# aux_board.net
KiCad netlist of a schematic drawn in EAGLE
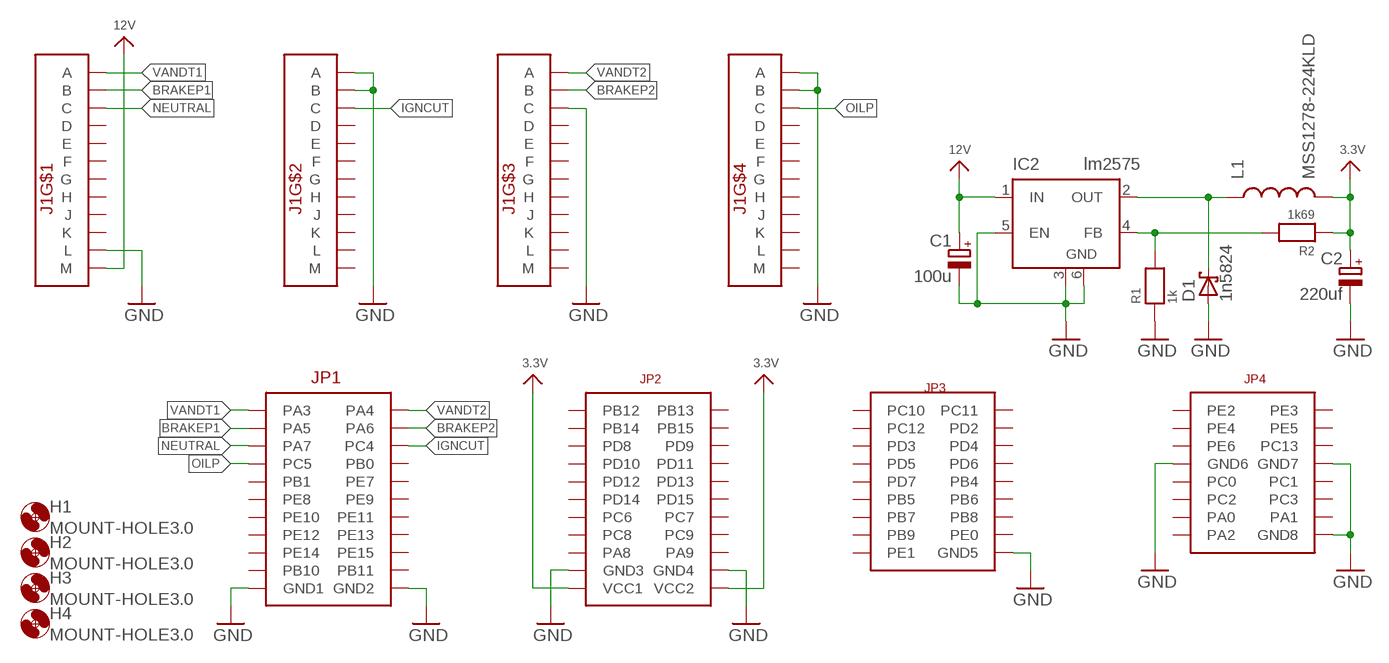
[diagram p0: schematic, sheet 1]

(export (version "E")
  (design (tool "Eeschema 10.0.6"))
  (components
    (comp (ref "C1")
      (value "100u")
      (footprint "eagle-import:E2,5-7")
      (libsource (lib "eagle-import") (part "CPOL-EUE2.5-7"))
    )
    (comp (ref "C2")
      (value "220uf")
      (footprint "eagle-import:E3,5-8")
      (libsource (lib "eagle-import") (part "CPOL-EUE3.5-8"))
    )
    (comp (ref "D1")
      (value "1n5824")
      (footprint "eagle-import:F126Z12")
      (libsource (lib "eagle-import") (part "SCHOTTKY-DIODEF126Z12"))
    )
    (comp (ref "H1")
      (value "MOUNT-HOLE3.0")
      (footprint "eagle-import:3,0")
      (libsource (lib "eagle-import") (part "MOUNT-HOLE3.0"))
    )
    (comp (ref "H2")
      (value "MOUNT-HOLE3.0")
      (footprint "eagle-import:3,0")
      (libsource (lib "eagle-import") (part "MOUNT-HOLE3.0"))
    )
    (comp (ref "H3")
      (value "MOUNT-HOLE3.0")
      (footprint "eagle-import:3,0")
      (libsource (lib "eagle-import") (part "MOUNT-HOLE3.0"))
    )
    (comp (ref "H4")
      (value "MOUNT-HOLE3.0")
      (footprint "eagle-import:3,0")
      (libsource (lib "eagle-import") (part "MOUNT-HOLE3.0"))
    )
    (comp (ref "IC2")
      (value "lm2575")
      (footprint "eagle-import:TO263-5")
      (libsource (lib "eagle-import") (part "LM2596S"))
    )
    (comp (ref "J1")
      (value "AUTOCONNECTOR")
      (footprint "eagle-import:AUTOCONNECTOR")
      (libsource (lib "eagle-import") (part "AUTOCONNECTOR"))
    )
    (comp (ref "L1")
      (value "MSS1278-224KLD")
      (footprint "eagle-import:CDRH125")
      (libsource (lib "eagle-import") (part "INDUCTORPWR"))
    )
    (comp (ref "R1")
      (value "1k")
      (footprint "eagle-import:_0603")
      (libsource (lib "eagle-import") (part "RESISTOR_0603"))
    )
    (comp (ref "R2")
      (value "1k69")
      (footprint "eagle-import:_0603")
      (libsource (lib "eagle-import") (part "RESISTOR_0603"))
    )
    (comp (ref "U$1")
      (value "CPU-BOARD")
      (footprint "eagle-import:CPU-BOARD-JP1")
      (libsource (lib "eagle-import") (part "CPU-BOARD"))
    )
  )
  (nets
    (net (code "1") (name "3.3V") (class "Default")
      (node (ref "C2") (pin "+") (pinfunction "+_+") (pintype "passive"))
      (node (ref "L1") (pin "2") (pinfunction "2_2") (pintype "passive"))
      (node (ref "R2") (pin "1") (pinfunction "1_1") (pintype "passive"))
      (node (ref "U$1") (pin "P$43") (pinfunction "VCC1_P$43") (pintype "bidirectional"))
      (node (ref "U$1") (pin "P$44") (pinfunction "VCC2_P$44") (pintype "bidirectional"))
    )
    (net (code "2") (name "12V") (class "Default")
      (node (ref "C1") (pin "+") (pinfunction "+_+") (pintype "passive"))
      (node (ref "IC2") (pin "1") (pinfunction "IN_1") (pintype "input"))
      (node (ref "J1") (pin "M1") (pinfunction "M_M1") (pintype "bidirectional"))
    )
    (net (code "3") (name "BRAKEP1") (class "Default")
      (node (ref "J1") (pin "B1") (pinfunction "B_B1") (pintype "bidirectional"))
      (node (ref "U$1") (pin "P$3") (pinfunction "PA5_P$3") (pintype "bidirectional"))
    )
    (net (code "4") (name "BRAKEP2") (class "Default")
      (node (ref "J1") (pin "B3") (pinfunction "B_B3") (pintype "bidirectional"))
      (node (ref "U$1") (pin "P$4") (pinfunction "PA6_P$4") (pintype "bidirectional"))
    )
    (net (code "5") (name "GND") (class "Default")
      (node (ref "C1") (pin "-") (pinfunction "-_-") (pintype "passive"))
      (node (ref "C2") (pin "-") (pinfunction "-_-") (pintype "passive"))
      (node (ref "D1") (pin "A") (pinfunction "A_A") (pintype "passive"))
      (node (ref "IC2") (pin "3") (pinfunction "GND_3") (pintype "power_in"))
      (node (ref "IC2") (pin "5") (pinfunction "EN_5") (pintype "input"))
      (node (ref "IC2") (pin "6") (pinfunction "GND_6") (pintype "power_in"))
      (node (ref "J1") (pin "A2") (pinfunction "A_A2") (pintype "bidirectional"))
      (node (ref "J1") (pin "A4") (pinfunction "A_A4") (pintype "bidirectional"))
      (node (ref "J1") (pin "B2") (pinfunction "B_B2") (pintype "bidirectional"))
      (node (ref "J1") (pin "B4") (pinfunction "B_B4") (pintype "bidirectional"))
      (node (ref "J1") (pin "C3") (pinfunction "C_C3") (pintype "bidirectional"))
      (node (ref "J1") (pin "L1") (pinfunction "L_L1") (pintype "bidirectional"))
      (node (ref "R1") (pin "1") (pinfunction "1_1") (pintype "passive"))
      (node (ref "U$1") (pin "P$21") (pinfunction "GND1_P$21") (pintype "bidirectional"))
      (node (ref "U$1") (pin "P$22") (pinfunction "GND2_P$22") (pintype "bidirectional"))
      (node (ref "U$1") (pin "P$41") (pinfunction "GND3_P$41") (pintype "bidirectional"))
      (node (ref "U$1") (pin "P$42") (pinfunction "GND4_P$42") (pintype "bidirectional"))
      (node (ref "U$1") (pin "P$62") (pinfunction "GND5_P$62") (pintype "bidirectional"))
      (node (ref "U$1") (pin "P$69") (pinfunction "GND6_P$69") (pintype "bidirectional"))
      (node (ref "U$1") (pin "P$70") (pinfunction "GND7_P$70") (pintype "bidirectional"))
      (node (ref "U$1") (pin "P$78") (pinfunction "GND8_P$78") (pintype "bidirectional"))
    )
    (net (code "6") (name "IGNCUT") (class "Default")
      (node (ref "J1") (pin "C2") (pinfunction "C_C2") (pintype "bidirectional"))
      (node (ref "U$1") (pin "P$6") (pinfunction "PC4_P$6") (pintype "bidirectional"))
    )
    (net (code "7") (name "NEUTRAL") (class "Default")
      (node (ref "J1") (pin "C1") (pinfunction "C_C1") (pintype "bidirectional"))
      (node (ref "U$1") (pin "P$5") (pinfunction "PA7_P$5") (pintype "bidirectional"))
    )
    (net (code "8") (name "Net-(IC2-FB)") (class "Default")
      (node (ref "IC2") (pin "4") (pinfunction "FB_4") (pintype "input"))
      (node (ref "R1") (pin "2") (pinfunction "2_2") (pintype "passive"))
      (node (ref "R2") (pin "2") (pinfunction "2_2") (pintype "passive"))
    )
    (net (code "9") (name "Net-(IC2-OUT)") (class "Default")
      (node (ref "D1") (pin "C") (pinfunction "C_C") (pintype "passive"))
      (node (ref "IC2") (pin "2") (pinfunction "OUT_2") (pintype "output"))
      (node (ref "L1") (pin "1") (pinfunction "1_1") (pintype "passive"))
    )
    (net (code "10") (name "OILP") (class "Default")
      (node (ref "J1") (pin "C4") (pinfunction "C_C4") (pintype "bidirectional"))
      (node (ref "U$1") (pin "P$7") (pinfunction "PC5_P$7") (pintype "bidirectional"))
    )
    (net (code "11") (name "VANDT1") (class "Default")
      (node (ref "J1") (pin "A1") (pinfunction "A_A1") (pintype "bidirectional"))
      (node (ref "U$1") (pin "P$1") (pinfunction "PA3_P$1") (pintype "bidirectional"))
    )
    (net (code "12") (name "VANDT2") (class "Default")
      (node (ref "J1") (pin "A3") (pinfunction "A_A3") (pintype "bidirectional"))
      (node (ref "U$1") (pin "P$2") (pinfunction "PA4_P$2") (pintype "bidirectional"))
    )
    (net (code "13") (name "unconnected-(J1A-D-PadD1)") (class "Default")
      (node (ref "J1") (pin "D1") (pinfunction "D_D1") (pintype "bidirectional"))
    )
    (net (code "14") (name "unconnected-(J1A-E-PadE1)") (class "Default")
      (node (ref "J1") (pin "E1") (pinfunction "E_E1") (pintype "bidirectional"))
    )
    (net (code "15") (name "unconnected-(J1A-F-PadF1)") (class "Default")
      (node (ref "J1") (pin "F1") (pinfunction "F_F1") (pintype "bidirectional"))
    )
    (net (code "16") (name "unconnected-(J1A-G-PadG1)") (class "Default")
      (node (ref "J1") (pin "G1") (pinfunction "G_G1") (pintype "bidirectional"))
    )
    (net (code "17") (name "unconnected-(J1A-H-PadH1)") (class "Default")
      (node (ref "J1") (pin "H1") (pinfunction "H_H1") (pintype "bidirectional"))
    )
    (net (code "18") (name "unconnected-(J1A-J-PadJ1)") (class "Default")
      (node (ref "J1") (pin "J1") (pinfunction "J_J1") (pintype "bidirectional"))
    )
    (net (code "19") (name "unconnected-(J1A-K-PadK1)") (class "Default")
      (node (ref "J1") (pin "K1") (pinfunction "K_K1") (pintype "bidirectional"))
    )
    (net (code "20") (name "unconnected-(J1B-D-PadD2)") (class "Default")
      (node (ref "J1") (pin "D2") (pinfunction "D_D2") (pintype "bidirectional"))
    )
    (net (code "21") (name "unconnected-(J1B-E-PadE2)") (class "Default")
      (node (ref "J1") (pin "E2") (pinfunction "E_E2") (pintype "bidirectional"))
    )
    (net (code "22") (name "unconnected-(J1B-F-PadF2)") (class "Default")
      (node (ref "J1") (pin "F2") (pinfunction "F_F2") (pintype "bidirectional"))
    )
    (net (code "23") (name "unconnected-(J1B-G-PadG2)") (class "Default")
      (node (ref "J1") (pin "G2") (pinfunction "G_G2") (pintype "bidirectional"))
    )
    (net (code "24") (name "unconnected-(J1B-H-PadH2)") (class "Default")
      (node (ref "J1") (pin "H2") (pinfunction "H_H2") (pintype "bidirectional"))
    )
    (net (code "25") (name "unconnected-(J1B-J-PadJ2)") (class "Default")
      (node (ref "J1") (pin "J2") (pinfunction "J_J2") (pintype "bidirectional"))
    )
    (net (code "26") (name "unconnected-(J1B-K-PadK2)") (class "Default")
      (node (ref "J1") (pin "K2") (pinfunction "K_K2") (pintype "bidirectional"))
    )
    (net (code "27") (name "unconnected-(J1B-L-PadL2)") (class "Default")
      (node (ref "J1") (pin "L2") (pinfunction "L_L2") (pintype "bidirectional"))
    )
    (net (code "28") (name "unconnected-(J1B-M-PadM2)") (class "Default")
      (node (ref "J1") (pin "M2") (pinfunction "M_M2") (pintype "bidirectional"))
    )
    (net (code "29") (name "unconnected-(J1C-D-PadD3)") (class "Default")
      (node (ref "J1") (pin "D3") (pinfunction "D_D3") (pintype "bidirectional"))
    )
    (net (code "30") (name "unconnected-(J1C-E-PadE3)") (class "Default")
      (node (ref "J1") (pin "E3") (pinfunction "E_E3") (pintype "bidirectional"))
    )
    (net (code "31") (name "unconnected-(J1C-F-PadF3)") (class "Default")
      (node (ref "J1") (pin "F3") (pinfunction "F_F3") (pintype "bidirectional"))
    )
    (net (code "32") (name "unconnected-(J1C-G-PadG3)") (class "Default")
      (node (ref "J1") (pin "G3") (pinfunction "G_G3") (pintype "bidirectional"))
    )
    (net (code "33") (name "unconnected-(J1C-H-PadH3)") (class "Default")
      (node (ref "J1") (pin "H3") (pinfunction "H_H3") (pintype "bidirectional"))
    )
    (net (code "34") (name "unconnected-(J1C-J-PadJ3)") (class "Default")
      (node (ref "J1") (pin "J3") (pinfunction "J_J3") (pintype "bidirectional"))
    )
    (net (code "35") (name "unconnected-(J1C-K-PadK3)") (class "Default")
      (node (ref "J1") (pin "K3") (pinfunction "K_K3") (pintype "bidirectional"))
    )
    (net (code "36") (name "unconnected-(J1C-L-PadL3)") (class "Default")
      (node (ref "J1") (pin "L3") (pinfunction "L_L3") (pintype "bidirectional"))
    )
    (net (code "37") (name "unconnected-(J1C-M-PadM3)") (class "Default")
      (node (ref "J1") (pin "M3") (pinfunction "M_M3") (pintype "bidirectional"))
    )
    (net (code "38") (name "unconnected-(J1D-D-PadD4)") (class "Default")
      (node (ref "J1") (pin "D4") (pinfunction "D_D4") (pintype "bidirectional"))
    )
    (net (code "39") (name "unconnected-(J1D-E-PadE4)") (class "Default")
      (node (ref "J1") (pin "E4") (pinfunction "E_E4") (pintype "bidirectional"))
    )
    (net (code "40") (name "unconnected-(J1D-F-PadF4)") (class "Default")
      (node (ref "J1") (pin "F4") (pinfunction "F_F4") (pintype "bidirectional"))
    )
    (net (code "41") (name "unconnected-(J1D-G-PadG4)") (class "Default")
      (node (ref "J1") (pin "G4") (pinfunction "G_G4") (pintype "bidirectional"))
    )
    (net (code "42") (name "unconnected-(J1D-H-PadH4)") (class "Default")
      (node (ref "J1") (pin "H4") (pinfunction "H_H4") (pintype "bidirectional"))
    )
    (net (code "43") (name "unconnected-(J1D-J-PadJ4)") (class "Default")
      (node (ref "J1") (pin "J4") (pinfunction "J_J4") (pintype "bidirectional"))
    )
    (net (code "44") (name "unconnected-(J1D-K-PadK4)") (class "Default")
      (node (ref "J1") (pin "K4") (pinfunction "K_K4") (pintype "bidirectional"))
    )
    (net (code "45") (name "unconnected-(J1D-L-PadL4)") (class "Default")
      (node (ref "J1") (pin "L4") (pinfunction "L_L4") (pintype "bidirectional"))
    )
    (net (code "46") (name "unconnected-(J1D-M-PadM4)") (class "Default")
      (node (ref "J1") (pin "M4") (pinfunction "M_M4") (pintype "bidirectional"))
    )
    (net (code "47") (name "unconnected-(U$1A-PB0-PadP$8)") (class "Default")
      (node (ref "U$1") (pin "P$8") (pinfunction "PB0_P$8") (pintype "bidirectional"))
    )
    (net (code "48") (name "unconnected-(U$1A-PB1-PadP$9)") (class "Default")
      (node (ref "U$1") (pin "P$9") (pinfunction "PB1_P$9") (pintype "bidirectional"))
    )
    (net (code "49") (name "unconnected-(U$1A-PB10-PadP$19)") (class "Default")
      (node (ref "U$1") (pin "P$19") (pinfunction "PB10_P$19") (pintype "bidirectional"))
    )
    (net (code "50") (name "unconnected-(U$1A-PB11-PadP$20)") (class "Default")
      (node (ref "U$1") (pin "P$20") (pinfunction "PB11_P$20") (pintype "bidirectional"))
    )
    (net (code "51") (name "unconnected-(U$1A-PE7-PadP$10)") (class "Default")
      (node (ref "U$1") (pin "P$10") (pinfunction "PE7_P$10") (pintype "bidirectional"))
    )
    (net (code "52") (name "unconnected-(U$1A-PE8-PadP$11)") (class "Default")
      (node (ref "U$1") (pin "P$11") (pinfunction "PE8_P$11") (pintype "bidirectional"))
    )
    (net (code "53") (name "unconnected-(U$1A-PE9-PadP$12)") (class "Default")
      (node (ref "U$1") (pin "P$12") (pinfunction "PE9_P$12") (pintype "bidirectional"))
    )
    (net (code "54") (name "unconnected-(U$1A-PE10-PadP$13)") (class "Default")
      (node (ref "U$1") (pin "P$13") (pinfunction "PE10_P$13") (pintype "bidirectional"))
    )
    (net (code "55") (name "unconnected-(U$1A-PE11-PadP$14)") (class "Default")
      (node (ref "U$1") (pin "P$14") (pinfunction "PE11_P$14") (pintype "bidirectional"))
    )
    (net (code "56") (name "unconnected-(U$1A-PE12-PadP$15)") (class "Default")
      (node (ref "U$1") (pin "P$15") (pinfunction "PE12_P$15") (pintype "bidirectional"))
    )
    (net (code "57") (name "unconnected-(U$1A-PE13-PadP$16)") (class "Default")
      (node (ref "U$1") (pin "P$16") (pinfunction "PE13_P$16") (pintype "bidirectional"))
    )
    (net (code "58") (name "unconnected-(U$1A-PE14-PadP$17)") (class "Default")
      (node (ref "U$1") (pin "P$17") (pinfunction "PE14_P$17") (pintype "bidirectional"))
    )
    (net (code "59") (name "unconnected-(U$1A-PE15-PadP$18)") (class "Default")
      (node (ref "U$1") (pin "P$18") (pinfunction "PE15_P$18") (pintype "bidirectional"))
    )
    (net (code "60") (name "unconnected-(U$1B-PA8-PadP$39)") (class "Default")
      (node (ref "U$1") (pin "P$39") (pinfunction "PA8_P$39") (pintype "bidirectional"))
    )
    (net (code "61") (name "unconnected-(U$1B-PA9-PadP$40)") (class "Default")
      (node (ref "U$1") (pin "P$40") (pinfunction "PA9_P$40") (pintype "bidirectional"))
    )
    (net (code "62") (name "unconnected-(U$1B-PB12-PadP$23)") (class "Default")
      (node (ref "U$1") (pin "P$23") (pinfunction "PB12_P$23") (pintype "bidirectional"))
    )
    (net (code "63") (name "unconnected-(U$1B-PB13-PadP$24)") (class "Default")
      (node (ref "U$1") (pin "P$24") (pinfunction "PB13_P$24") (pintype "bidirectional"))
    )
    (net (code "64") (name "unconnected-(U$1B-PB14-PadP$25)") (class "Default")
      (node (ref "U$1") (pin "P$25") (pinfunction "PB14_P$25") (pintype "bidirectional"))
    )
    (net (code "65") (name "unconnected-(U$1B-PB15-PadP$26)") (class "Default")
      (node (ref "U$1") (pin "P$26") (pinfunction "PB15_P$26") (pintype "bidirectional"))
    )
    (net (code "66") (name "unconnected-(U$1B-PC6-PadP$35)") (class "Default")
      (node (ref "U$1") (pin "P$35") (pinfunction "PC6_P$35") (pintype "bidirectional"))
    )
    (net (code "67") (name "unconnected-(U$1B-PC7-PadP$36)") (class "Default")
      (node (ref "U$1") (pin "P$36") (pinfunction "PC7_P$36") (pintype "bidirectional"))
    )
    (net (code "68") (name "unconnected-(U$1B-PC8-PadP$37)") (class "Default")
      (node (ref "U$1") (pin "P$37") (pinfunction "PC8_P$37") (pintype "bidirectional"))
    )
    (net (code "69") (name "unconnected-(U$1B-PC9-PadP$38)") (class "Default")
      (node (ref "U$1") (pin "P$38") (pinfunction "PC9_P$38") (pintype "bidirectional"))
    )
    (net (code "70") (name "unconnected-(U$1B-PD8-PadP$27)") (class "Default")
      (node (ref "U$1") (pin "P$27") (pinfunction "PD8_P$27") (pintype "bidirectional"))
    )
    (net (code "71") (name "unconnected-(U$1B-PD9-PadP$28)") (class "Default")
      (node (ref "U$1") (pin "P$28") (pinfunction "PD9_P$28") (pintype "bidirectional"))
    )
    (net (code "72") (name "unconnected-(U$1B-PD10-PadP$29)") (class "Default")
      (node (ref "U$1") (pin "P$29") (pinfunction "PD10_P$29") (pintype "bidirectional"))
    )
    (net (code "73") (name "unconnected-(U$1B-PD11-PadP$30)") (class "Default")
      (node (ref "U$1") (pin "P$30") (pinfunction "PD11_P$30") (pintype "bidirectional"))
    )
    (net (code "74") (name "unconnected-(U$1B-PD12-PadP$31)") (class "Default")
      (node (ref "U$1") (pin "P$31") (pinfunction "PD12_P$31") (pintype "bidirectional"))
    )
    (net (code "75") (name "unconnected-(U$1B-PD13-PadP$32)") (class "Default")
      (node (ref "U$1") (pin "P$32") (pinfunction "PD13_P$32") (pintype "bidirectional"))
    )
    (net (code "76") (name "unconnected-(U$1B-PD14-PadP$33)") (class "Default")
      (node (ref "U$1") (pin "P$33") (pinfunction "PD14_P$33") (pintype "bidirectional"))
    )
    (net (code "77") (name "unconnected-(U$1B-PD15-PadP$34)") (class "Default")
      (node (ref "U$1") (pin "P$34") (pinfunction "PD15_P$34") (pintype "bidirectional"))
    )
    (net (code "78") (name "unconnected-(U$1C-PB4-PadP$54)") (class "Default")
      (node (ref "U$1") (pin "P$54") (pinfunction "PB4_P$54") (pintype "bidirectional"))
    )
    (net (code "79") (name "unconnected-(U$1C-PB5-PadP$55)") (class "Default")
      (node (ref "U$1") (pin "P$55") (pinfunction "PB5_P$55") (pintype "bidirectional"))
    )
    (net (code "80") (name "unconnected-(U$1C-PB6-PadP$56)") (class "Default")
      (node (ref "U$1") (pin "P$56") (pinfunction "PB6_P$56") (pintype "bidirectional"))
    )
    (net (code "81") (name "unconnected-(U$1C-PB7-PadP$57)") (class "Default")
      (node (ref "U$1") (pin "P$57") (pinfunction "PB7_P$57") (pintype "bidirectional"))
    )
    (net (code "82") (name "unconnected-(U$1C-PB8-PadP$58)") (class "Default")
      (node (ref "U$1") (pin "P$58") (pinfunction "PB8_P$58") (pintype "bidirectional"))
    )
    (net (code "83") (name "unconnected-(U$1C-PB9-PadP$59)") (class "Default")
      (node (ref "U$1") (pin "P$59") (pinfunction "PB9_P$59") (pintype "bidirectional"))
    )
    (net (code "84") (name "unconnected-(U$1C-PC10-PadP$45)") (class "Default")
      (node (ref "U$1") (pin "P$45") (pinfunction "PC10_P$45") (pintype "bidirectional"))
    )
    (net (code "85") (name "unconnected-(U$1C-PC11-PadP$46)") (class "Default")
      (node (ref "U$1") (pin "P$46") (pinfunction "PC11_P$46") (pintype "bidirectional"))
    )
    (net (code "86") (name "unconnected-(U$1C-PC12-PadP$47)") (class "Default")
      (node (ref "U$1") (pin "P$47") (pinfunction "PC12_P$47") (pintype "bidirectional"))
    )
    (net (code "87") (name "unconnected-(U$1C-PD2-PadP$48)") (class "Default")
      (node (ref "U$1") (pin "P$48") (pinfunction "PD2_P$48") (pintype "bidirectional"))
    )
    (net (code "88") (name "unconnected-(U$1C-PD3-PadP$49)") (class "Default")
      (node (ref "U$1") (pin "P$49") (pinfunction "PD3_P$49") (pintype "bidirectional"))
    )
    (net (code "89") (name "unconnected-(U$1C-PD4-PadP$50)") (class "Default")
      (node (ref "U$1") (pin "P$50") (pinfunction "PD4_P$50") (pintype "bidirectional"))
    )
    (net (code "90") (name "unconnected-(U$1C-PD5-PadP$51)") (class "Default")
      (node (ref "U$1") (pin "P$51") (pinfunction "PD5_P$51") (pintype "bidirectional"))
    )
    (net (code "91") (name "unconnected-(U$1C-PD6-PadP$52)") (class "Default")
      (node (ref "U$1") (pin "P$52") (pinfunction "PD6_P$52") (pintype "bidirectional"))
    )
    (net (code "92") (name "unconnected-(U$1C-PD7-PadP$53)") (class "Default")
      (node (ref "U$1") (pin "P$53") (pinfunction "PD7_P$53") (pintype "bidirectional"))
    )
    (net (code "93") (name "unconnected-(U$1C-PE0-PadP$60)") (class "Default")
      (node (ref "U$1") (pin "P$60") (pinfunction "PE0_P$60") (pintype "bidirectional"))
    )
    (net (code "94") (name "unconnected-(U$1C-PE1-PadP$61)") (class "Default")
      (node (ref "U$1") (pin "P$61") (pinfunction "PE1_P$61") (pintype "bidirectional"))
    )
    (net (code "95") (name "unconnected-(U$1D-PA0-PadP$75)") (class "Default")
      (node (ref "U$1") (pin "P$75") (pinfunction "PA0_P$75") (pintype "bidirectional"))
    )
    (net (code "96") (name "unconnected-(U$1D-PA1-PadP$76)") (class "Default")
      (node (ref "U$1") (pin "P$76") (pinfunction "PA1_P$76") (pintype "bidirectional"))
    )
    (net (code "97") (name "unconnected-(U$1D-PA2-PadP$77)") (class "Default")
      (node (ref "U$1") (pin "P$77") (pinfunction "PA2_P$77") (pintype "bidirectional"))
    )
    (net (code "98") (name "unconnected-(U$1D-PC0-PadP$71)") (class "Default")
      (node (ref "U$1") (pin "P$71") (pinfunction "PC0_P$71") (pintype "bidirectional"))
    )
    (net (code "99") (name "unconnected-(U$1D-PC1-PadP$72)") (class "Default")
      (node (ref "U$1") (pin "P$72") (pinfunction "PC1_P$72") (pintype "bidirectional"))
    )
    (net (code "100") (name "unconnected-(U$1D-PC2-PadP$73)") (class "Default")
      (node (ref "U$1") (pin "P$73") (pinfunction "PC2_P$73") (pintype "bidirectional"))
    )
    (net (code "101") (name "unconnected-(U$1D-PC3-PadP$74)") (class "Default")
      (node (ref "U$1") (pin "P$74") (pinfunction "PC3_P$74") (pintype "bidirectional"))
    )
    (net (code "102") (name "unconnected-(U$1D-PC13-PadP$68)") (class "Default")
      (node (ref "U$1") (pin "P$68") (pinfunction "PC13_P$68") (pintype "bidirectional"))
    )
    (net (code "103") (name "unconnected-(U$1D-PE2-PadP$63)") (class "Default")
      (node (ref "U$1") (pin "P$63") (pinfunction "PE2_P$63") (pintype "bidirectional"))
    )
    (net (code "104") (name "unconnected-(U$1D-PE3-PadP$64)") (class "Default")
      (node (ref "U$1") (pin "P$64") (pinfunction "PE3_P$64") (pintype "bidirectional"))
    )
    (net (code "105") (name "unconnected-(U$1D-PE4-PadP$65)") (class "Default")
      (node (ref "U$1") (pin "P$65") (pinfunction "PE4_P$65") (pintype "bidirectional"))
    )
    (net (code "106") (name "unconnected-(U$1D-PE5-PadP$66)") (class "Default")
      (node (ref "U$1") (pin "P$66") (pinfunction "PE5_P$66") (pintype "bidirectional"))
    )
    (net (code "107") (name "unconnected-(U$1D-PE6-PadP$67)") (class "Default")
      (node (ref "U$1") (pin "P$67") (pinfunction "PE6_P$67") (pintype "bidirectional"))
    )
  )
)
